# 25632-myersd33_02_7459.net
KiCad netlist of a schematic drawn in Altium Designer
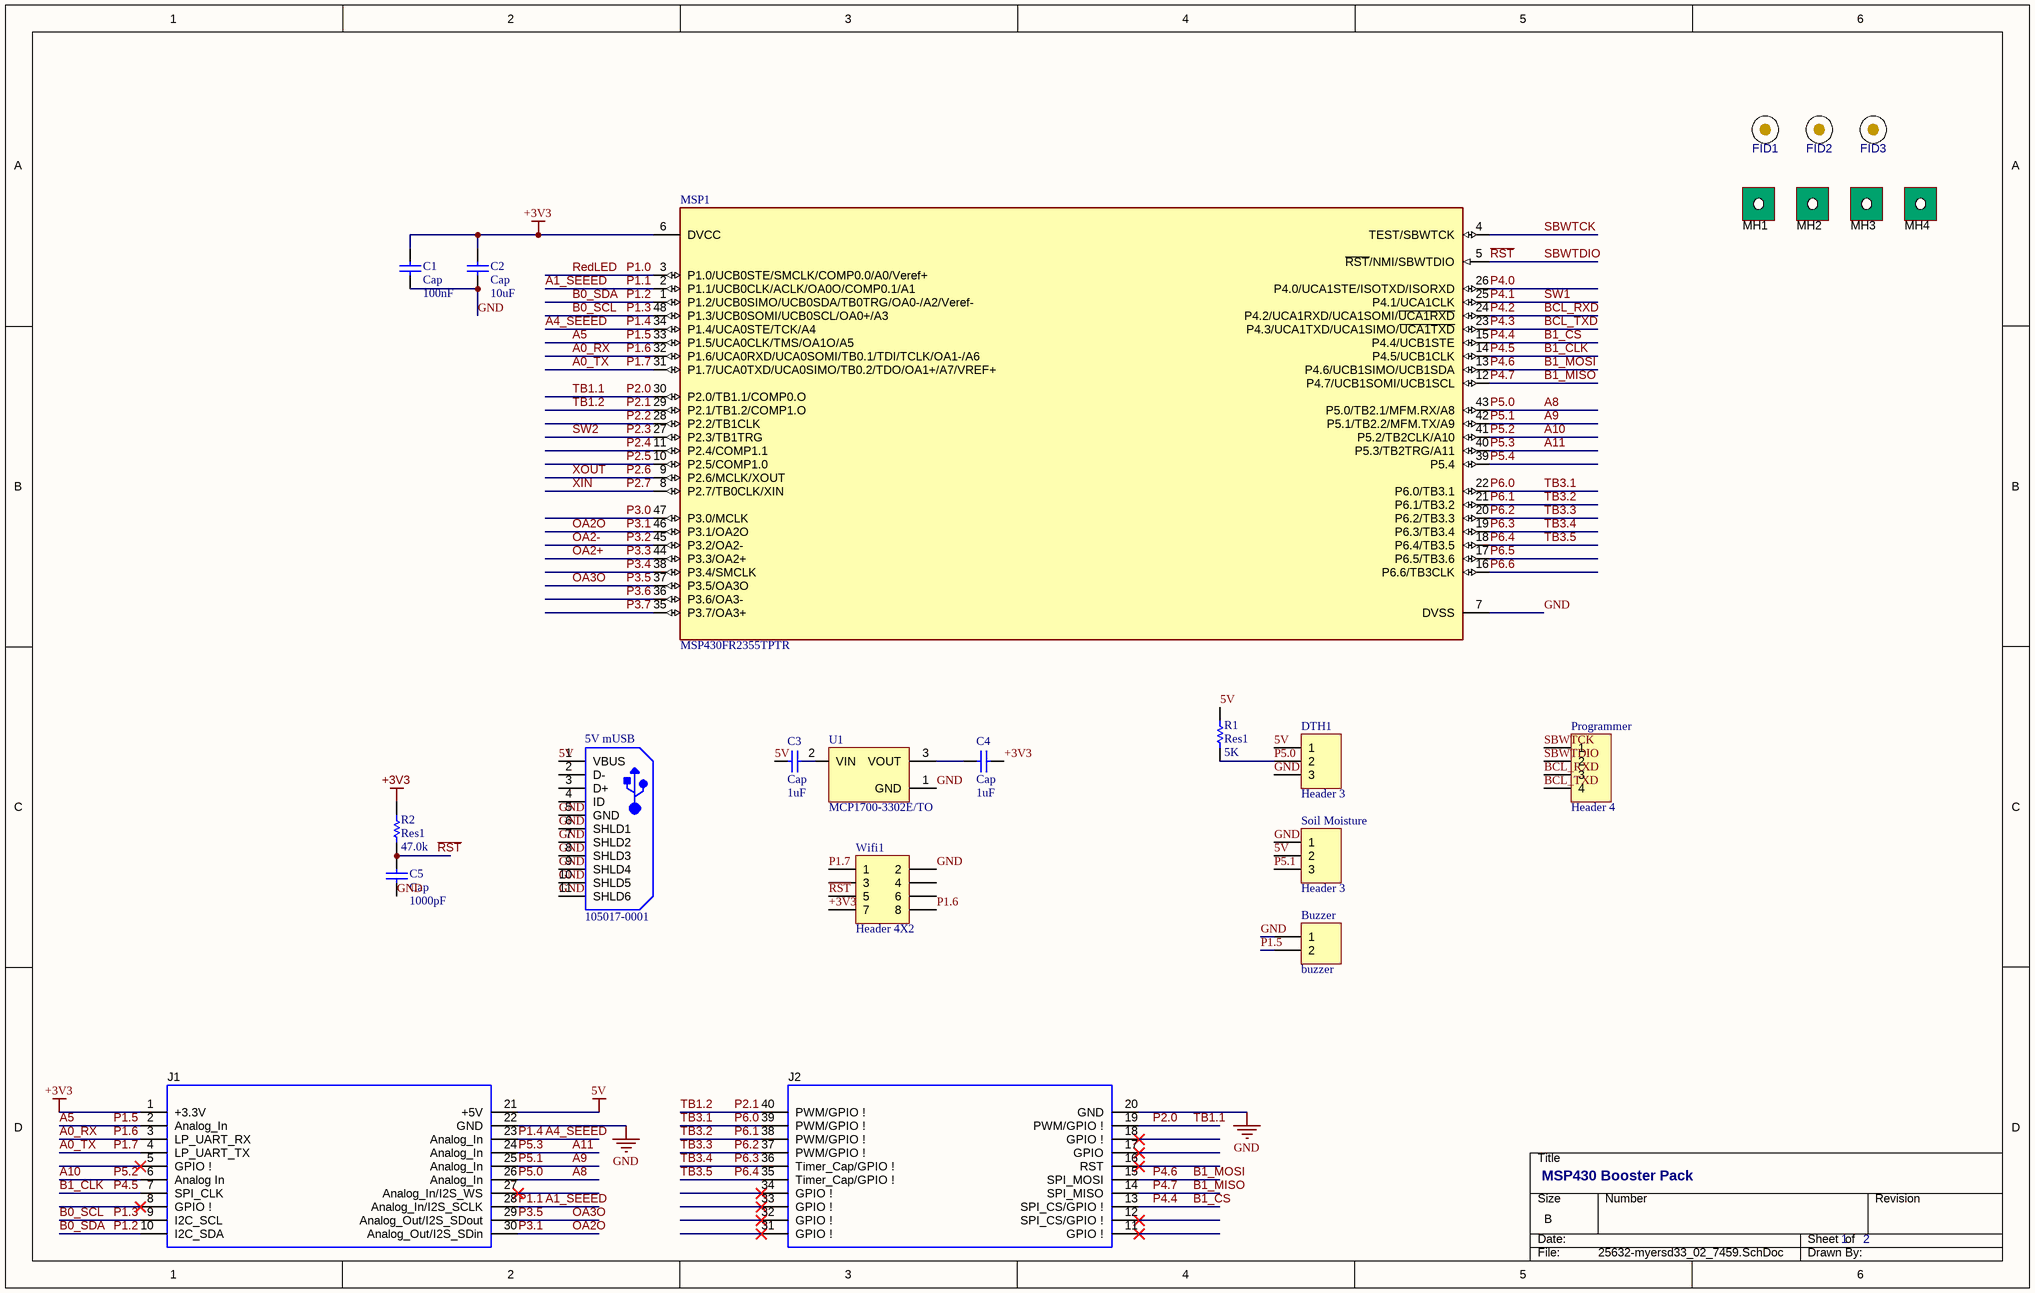
[diagram p0: 25632-myersd33_02_7459.SchDoc]

(export (version "E")
  (design (tool "Eeschema 10.0.6"))
  (components
    (comp (ref "5V mUSB")
      (value "105017-0001")
      (footprint "USB-MICRO-B_V")
      (fields (field (name "MANUFACTURER") "Molex"))
      (libsource (lib "Altium Content Vault") (part "USB-5-6SHLD"))
    )
    (comp (ref "Buzzer")
      (value "buzzer")
      (footprint "HDR1X2")
      (description "Header, 2-Pin")
      (fields (field (name "PUBLISHER") "Altium Limited"))
      (libsource (lib "Miscellaneous Connectors") (part "Header 2"))
    )
    (comp (ref "C1")
      (value "Cap")
      (footprint "RAD-0.3")
      (description "Capacitor")
      (fields (field (name "ALTIUM_VALUE") "100nF") (field (name "PUBLISHER") "Altium Limited"))
      (libsource (lib "Miscellaneous Devices") (part "Cap"))
    )
    (comp (ref "C2")
      (value "Cap")
      (footprint "RAD-0.3")
      (description "Capacitor")
      (fields (field (name "ALTIUM_VALUE") "10uF") (field (name "PUBLISHER") "Altium Limited"))
      (libsource (lib "Miscellaneous Devices") (part "Cap"))
    )
    (comp (ref "C3")
      (value "Cap")
      (footprint "RAD-0.3")
      (description "Capacitor")
      (fields (field (name "ALTIUM_VALUE") "1uF") (field (name "PUBLISHER") "Altium Limited"))
      (libsource (lib "Miscellaneous Devices") (part "Cap"))
    )
    (comp (ref "C4")
      (value "Cap")
      (footprint "RAD-0.3")
      (description "Capacitor")
      (fields (field (name "ALTIUM_VALUE") "1uF") (field (name "PUBLISHER") "Altium Limited"))
      (libsource (lib "Miscellaneous Devices") (part "Cap"))
    )
    (comp (ref "C5")
      (value "Cap")
      (footprint "RAD-0.3")
      (description "Capacitor")
      (fields (field (name "ALTIUM_VALUE") "1000pF") (field (name "PUBLISHER") "Altium Limited"))
      (libsource (lib "Miscellaneous Devices") (part "Cap"))
    )
    (comp (ref "DTH1")
      (value "Header 3")
      (footprint "HDR1X3")
      (description "Header, 3-Pin")
      (fields (field (name "PUBLISHER") "Altium Limited"))
      (libsource (lib "Miscellaneous Connectors") (part "Header 3"))
    )
    (comp (ref "FID1")
      (value "Fiducial")
      (footprint "Fiducial6.4-20")
      (description "Fiducial mark.  There is nothing to buy or mount.")
      (fields (field (name "SYMBOLCREATOR") "codlsc") (field (name "PUBLISHER") "Texas Instruments"))
      (libsource (lib "MiscParts") (part "Fiducial"))
    )
    (comp (ref "FID2")
      (value "Fiducial")
      (footprint "Fiducial6.4-20")
      (description "Fiducial mark.  There is nothing to buy or mount.")
      (fields (field (name "SYMBOLCREATOR") "codlsc") (field (name "PUBLISHER") "Texas Instruments"))
      (libsource (lib "MiscParts") (part "Fiducial"))
    )
    (comp (ref "FID3")
      (value "Fiducial")
      (footprint "Fiducial6.4-20")
      (description "Fiducial mark.  There is nothing to buy or mount.")
      (fields (field (name "SYMBOLCREATOR") "codlsc") (field (name "PUBLISHER") "Texas Instruments"))
      (libsource (lib "MiscParts") (part "Fiducial"))
    )
    (comp (ref "J1")
      (value "SSQ-110-03-T-D")
      (footprint "BoosterPack_40pin_J1J3")
      (description "Receptacle, 2.54mm, 10x2, Tin, TH")
      (fields
        (field (name "MANUFACTURER") "Samtec")
        (field (name "ALTERNATE PARTNUMBER") "CRD-081413-A-G")
        (field (name "SYMBOLCREATOR") "a0412235")
        (field (name "PUBLISHER") "Texas Instruments")
      )
      (libsource (lib "Hardware") (part "BoosterPack_40pin_J1J3"))
    )
    (comp (ref "J2")
      (value "SSQ-110-03-T-D")
      (footprint "BoosterPack_40pin_J2J4")
      (description "Receptacle, 2.54mm, 10x2, Tin, TH")
      (fields
        (field (name "MANUFACTURER") "Samtec")
        (field (name "ALTERNATE PARTNUMBER") "CRD-081413-A-G")
        (field (name "SYMBOLCREATOR") "a0412235")
        (field (name "PUBLISHER") "Texas Instruments")
      )
      (libsource (lib "Hardware") (part "BoosterPack_40pin_J2J4"))
    )
    (comp (ref "MH1")
      (value "MTG_NoPads")
      (footprint "NPTH125mil")
      (description "PCB Mounting Hole, No Pad")
      (fields
        (field (name "MANUFACTURER") "Any")
        (field (name "SYMBOLCREATOR") "a0412235")
        (field (name "PUBLISHER") "Texas Instruments")
      )
      (libsource (lib "Hardware") (part "Mounting Hole (non-standard) No Pad"))
    )
    (comp (ref "MH2")
      (value "MTG_NoPads")
      (footprint "NPTH125mil")
      (description "PCB Mounting Hole, No Pad")
      (fields
        (field (name "MANUFACTURER") "Any")
        (field (name "SYMBOLCREATOR") "a0412235")
        (field (name "PUBLISHER") "Texas Instruments")
      )
      (libsource (lib "Hardware") (part "Mounting Hole (non-standard) No Pad"))
    )
    (comp (ref "MH3")
      (value "MTG_NoPads")
      (footprint "NPTH125mil")
      (description "PCB Mounting Hole, No Pad")
      (fields
        (field (name "MANUFACTURER") "Any")
        (field (name "SYMBOLCREATOR") "a0412235")
        (field (name "PUBLISHER") "Texas Instruments")
      )
      (libsource (lib "Hardware") (part "Mounting Hole (non-standard) No Pad"))
    )
    (comp (ref "MH4")
      (value "MTG_NoPads")
      (footprint "NPTH125mil")
      (description "PCB Mounting Hole, No Pad")
      (fields
        (field (name "MANUFACTURER") "Any")
        (field (name "SYMBOLCREATOR") "a0412235")
        (field (name "PUBLISHER") "Texas Instruments")
      )
      (libsource (lib "Hardware") (part "Mounting Hole (non-standard) No Pad"))
    )
    (comp (ref "MSP1")
      (value "MSP430FR2355TPTR")
      (footprint "FP-PT0048A-MFG")
      (description "IC MCU 16BIT 32KB FRAM 48LQFP")
      (fields
        (field (name "MANUFACTURER") "Texas Instruments")
        (field (name "OCTOPART") "https://octopart.com/msp430fr2355tptr-texas+instruments-92191342")
      )
      (libsource (lib "Altium Content Vault") (part "bd983ca6877cdd146f198514b3acb3b"))
    )
    (comp (ref "Programmer")
      (value "Header 4")
      (footprint "HDR1X4")
      (description "Header, 4-Pin")
      (fields (field (name "PUBLISHER") "Altium Limited"))
      (libsource (lib "Miscellaneous Connectors") (part "Header 4"))
    )
    (comp (ref "R1")
      (value "Res1")
      (footprint "AXIAL-0.3")
      (description "Resistor")
      (fields (field (name "ALTIUM_VALUE") "5K") (field (name "PUBLISHER") "Altium Limited"))
      (libsource (lib "Miscellaneous Devices") (part "Res1"))
    )
    (comp (ref "R2")
      (value "Res1")
      (footprint "AXIAL-0.3")
      (description "Resistor")
      (fields (field (name "ALTIUM_VALUE") "47.0k") (field (name "PUBLISHER") "Altium Limited"))
      (libsource (lib "Miscellaneous Devices") (part "Res1"))
    )
    (comp (ref "Soil Moisture")
      (value "Header 3")
      (footprint "HDR1X3")
      (description "Header, 3-Pin")
      (fields (field (name "PUBLISHER") "Altium Limited"))
      (libsource (lib "Miscellaneous Connectors") (part "Header 3"))
    )
    (comp (ref "U1")
      (value "MCP1700-3302E/TO")
      (footprint "TO-92-TO3")
      (description "Low Quiescent Current LDO, 3-Pin TO-92, Extended TemperatureBAG")
      (libsource (lib "Altium Content Vault") (part "PM-LINEREG-MCP1700-IL3B"))
    )
    (comp (ref "Wifi1")
      (value "Header 4X2")
      (footprint "HDR2X4")
      (description "Header, 4-Pin, Dual row")
      (fields (field (name "PUBLISHER") "Altium Limited"))
      (libsource (lib "Miscellaneous Connectors") (part "Header 4X2"))
    )
  )
  (nets
    (net (code "1") (name "+3V3") (class "Default")
      (node (ref "C1") (pin "2") (pinfunction "2_2") (pintype "passive"))
      (node (ref "C2") (pin "2") (pinfunction "2_2") (pintype "passive"))
      (node (ref "C4") (pin "2") (pinfunction "2_2") (pintype "passive"))
      (node (ref "J1") (pin "1") (pinfunction "+3.3V_1") (pintype "power_in"))
      (node (ref "MSP1") (pin "6") (pinfunction "DVCC_6") (pintype "power_in"))
      (node (ref "R2") (pin "2") (pinfunction "2_2") (pintype "passive"))
      (node (ref "Wifi1") (pin "7") (pinfunction "7_7") (pintype "passive"))
    )
    (net (code "2") (name "/A0_RX") (class "Default")
      (node (ref "J1") (pin "3") (pinfunction "LP_UART_RX_3") (pintype "passive"))
      (node (ref "MSP1") (pin "32") (pinfunction "P1.6/UCA0RXD/UCA0SOMI/TB0.1/TDI/TCLK/OA1-/A6_32") (pintype "bidirectional"))
      (node (ref "Wifi1") (pin "8") (pinfunction "8_8") (pintype "passive"))
    )
    (net (code "3") (name "/A0_TX") (class "Default")
      (node (ref "J1") (pin "4") (pinfunction "LP_UART_TX_4") (pintype "passive"))
      (node (ref "MSP1") (pin "31") (pinfunction "P1.7/UCA0TXD/UCA0SIMO/TB0.2/TDO/OA1+/A7/VREF+_31") (pintype "bidirectional"))
      (node (ref "Wifi1") (pin "1") (pinfunction "1_1") (pintype "passive"))
    )
    (net (code "4") (name "/A1_SEEED") (class "Default")
      (node (ref "J1") (pin "28") (pinfunction "Analog_In/I2S_SCLK_28") (pintype "passive"))
      (node (ref "MSP1") (pin "2") (pinfunction "P1.1/UCB0CLK/ACLK/OA0O/COMP0.1/A1_2") (pintype "bidirectional"))
    )
    (net (code "5") (name "/A4_SEEED") (class "Default")
      (node (ref "J1") (pin "23") (pinfunction "Analog_In_23") (pintype "passive"))
      (node (ref "MSP1") (pin "34") (pinfunction "P1.4/UCA0STE/TCK/A4_34") (pintype "bidirectional"))
    )
    (net (code "6") (name "/A5") (class "Default")
      (node (ref "Buzzer") (pin "2") (pinfunction "2_2") (pintype "passive"))
      (node (ref "J1") (pin "2") (pinfunction "Analog_In_2") (pintype "passive"))
      (node (ref "MSP1") (pin "33") (pinfunction "P1.5/UCA0CLK/TMS/OA1O/A5_33") (pintype "bidirectional"))
    )
    (net (code "7") (name "/A8") (class "Default")
      (node (ref "DTH1") (pin "2") (pinfunction "2_2") (pintype "passive"))
      (node (ref "J1") (pin "26") (pinfunction "Analog_In_26") (pintype "passive"))
      (node (ref "MSP1") (pin "43") (pinfunction "P5.0/TB2.1/MFM.RX/A8_43") (pintype "bidirectional"))
      (node (ref "R1") (pin "1") (pinfunction "1_1") (pintype "passive"))
    )
    (net (code "8") (name "/A9") (class "Default")
      (node (ref "J1") (pin "25") (pinfunction "Analog_In_25") (pintype "passive"))
      (node (ref "MSP1") (pin "42") (pinfunction "P5.1/TB2.2/MFM.TX/A9_42") (pintype "bidirectional"))
      (node (ref "Soil Moisture") (pin "3") (pinfunction "3_3") (pintype "passive"))
    )
    (net (code "9") (name "/A10") (class "Default")
      (node (ref "J1") (pin "6") (pinfunction "Analog_In_6") (pintype "passive"))
      (node (ref "MSP1") (pin "41") (pinfunction "P5.2/TB2CLK/A10_41") (pintype "bidirectional"))
    )
    (net (code "10") (name "/A11") (class "Default")
      (node (ref "J1") (pin "24") (pinfunction "Analog_In_24") (pintype "passive"))
      (node (ref "MSP1") (pin "40") (pinfunction "P5.3/TB2TRG/A11_40") (pintype "bidirectional"))
    )
    (net (code "11") (name "/B0_SCL") (class "Default")
      (node (ref "J1") (pin "9") (pinfunction "I2C_SCL_9") (pintype "passive"))
      (node (ref "MSP1") (pin "48") (pinfunction "P1.3/UCB0SOMI/UCB0SCL/OA0+/A3_48") (pintype "bidirectional"))
    )
    (net (code "12") (name "/B0_SDA") (class "Default")
      (node (ref "J1") (pin "10") (pinfunction "I2C_SDA_10") (pintype "passive"))
      (node (ref "MSP1") (pin "1") (pinfunction "P1.2/UCB0SIMO/UCB0SDA/TB0TRG/OA0-/A2/Veref-_1") (pintype "bidirectional"))
    )
    (net (code "13") (name "/B1_CLK") (class "Default")
      (node (ref "J1") (pin "7") (pinfunction "SPI_CLK_7") (pintype "passive"))
      (node (ref "MSP1") (pin "14") (pinfunction "P4.5/UCB1CLK_14") (pintype "bidirectional"))
    )
    (net (code "14") (name "/B1_CS") (class "Default")
      (node (ref "J2") (pin "13") (pinfunction "SPI_CS/GPIO_!_13") (pintype "passive"))
      (node (ref "MSP1") (pin "15") (pinfunction "P4.4/UCB1STE_15") (pintype "bidirectional"))
    )
    (net (code "15") (name "/B1_MISO") (class "Default")
      (node (ref "J2") (pin "14") (pinfunction "SPI_MISO_14") (pintype "passive"))
      (node (ref "MSP1") (pin "12") (pinfunction "P4.7/UCB1SOMI/UCB1SCL_12") (pintype "bidirectional"))
    )
    (net (code "16") (name "/B1_MOSI") (class "Default")
      (node (ref "J2") (pin "15") (pinfunction "SPI_MOSI_15") (pintype "passive"))
      (node (ref "MSP1") (pin "13") (pinfunction "P4.6/UCB1SIMO/UCB1SDA_13") (pintype "bidirectional"))
    )
    (net (code "17") (name "/BCL_RXD") (class "Default")
      (node (ref "MSP1") (pin "24") (pinfunction "P4.2/UCA1RXD/UCA1SOMI/~{UCA1RXD}_24") (pintype "bidirectional"))
      (node (ref "Programmer") (pin "3") (pinfunction "3_3") (pintype "passive"))
    )
    (net (code "18") (name "/BCL_TXD") (class "Default")
      (node (ref "MSP1") (pin "23") (pinfunction "P4.3/UCA1TXD/UCA1SIMO/~{UCA1TXD}_23") (pintype "bidirectional"))
      (node (ref "Programmer") (pin "4") (pinfunction "4_4") (pintype "passive"))
    )
    (net (code "19") (name "/OA2+") (class "Default")
      (node (ref "MSP1") (pin "44") (pinfunction "P3.3/OA2+_44") (pintype "bidirectional"))
    )
    (net (code "20") (name "/OA2-") (class "Default")
      (node (ref "MSP1") (pin "45") (pinfunction "P3.2/OA2-_45") (pintype "bidirectional"))
    )
    (net (code "21") (name "/OA2O") (class "Default")
      (node (ref "J1") (pin "30") (pinfunction "Analog_Out/I2S_SDin_30") (pintype "passive"))
      (node (ref "MSP1") (pin "46") (pinfunction "P3.1/OA2O_46") (pintype "bidirectional"))
    )
    (net (code "22") (name "/OA3O") (class "Default")
      (node (ref "J1") (pin "29") (pinfunction "Analog_Out/I2S_SDout_29") (pintype "passive"))
      (node (ref "MSP1") (pin "37") (pinfunction "P3.5/OA3O_37") (pintype "bidirectional"))
    )
    (net (code "23") (name "/P1.0") (class "Default")
      (node (ref "MSP1") (pin "3") (pinfunction "P1.0/UCB0STE/SMCLK/COMP0.0/A0/Veref+_3") (pintype "bidirectional"))
    )
    (net (code "24") (name "/P2.0") (class "Default")
      (node (ref "J2") (pin "19") (pinfunction "PWM/GPIO_!_19") (pintype "passive"))
      (node (ref "MSP1") (pin "30") (pinfunction "P2.0/TB1.1/COMP0.O_30") (pintype "bidirectional"))
    )
    (net (code "25") (name "/P2.1") (class "Default")
      (node (ref "J2") (pin "40") (pinfunction "PWM/GPIO_!_40") (pintype "passive"))
      (node (ref "MSP1") (pin "29") (pinfunction "P2.1/TB1.2/COMP1.O_29") (pintype "bidirectional"))
    )
    (net (code "26") (name "/P2.2") (class "Default")
      (node (ref "MSP1") (pin "28") (pinfunction "P2.2/TB1CLK_28") (pintype "bidirectional"))
    )
    (net (code "27") (name "/P2.3") (class "Default")
      (node (ref "MSP1") (pin "27") (pinfunction "P2.3/TB1TRG_27") (pintype "bidirectional"))
    )
    (net (code "28") (name "/P2.4") (class "Default")
      (node (ref "MSP1") (pin "11") (pinfunction "P2.4/COMP1.1_11") (pintype "bidirectional"))
    )
    (net (code "29") (name "/P2.5") (class "Default")
      (node (ref "MSP1") (pin "10") (pinfunction "P2.5/COMP1.0_10") (pintype "bidirectional"))
    )
    (net (code "30") (name "/P2.6") (class "Default")
      (node (ref "MSP1") (pin "9") (pinfunction "P2.6/MCLK/XOUT_9") (pintype "bidirectional"))
    )
    (net (code "31") (name "/P2.7") (class "Default")
      (node (ref "MSP1") (pin "8") (pinfunction "P2.7/TB0CLK/XIN_8") (pintype "bidirectional"))
    )
    (net (code "32") (name "/P3.0") (class "Default")
      (node (ref "MSP1") (pin "47") (pinfunction "P3.0/MCLK_47") (pintype "bidirectional"))
    )
    (net (code "33") (name "/P3.4") (class "Default")
      (node (ref "MSP1") (pin "38") (pinfunction "P3.4/SMCLK_38") (pintype "bidirectional"))
    )
    (net (code "34") (name "/P3.6") (class "Default")
      (node (ref "MSP1") (pin "36") (pinfunction "P3.6/OA3-_36") (pintype "bidirectional"))
    )
    (net (code "35") (name "/P3.7") (class "Default")
      (node (ref "MSP1") (pin "35") (pinfunction "P3.7/OA3+_35") (pintype "bidirectional"))
    )
    (net (code "36") (name "/P4.0") (class "Default")
      (node (ref "MSP1") (pin "26") (pinfunction "P4.0/UCA1STE/ISOTXD/ISORXD_26") (pintype "bidirectional"))
    )
    (net (code "37") (name "/P4.1") (class "Default")
      (node (ref "MSP1") (pin "25") (pinfunction "P4.1/UCA1CLK_25") (pintype "bidirectional"))
    )
    (net (code "38") (name "/P5.4") (class "Default")
      (node (ref "MSP1") (pin "39") (pinfunction "P5.4_39") (pintype "bidirectional"))
    )
    (net (code "39") (name "/P6.0") (class "Default")
      (node (ref "J2") (pin "39") (pinfunction "PWM/GPIO_!_39") (pintype "passive"))
      (node (ref "MSP1") (pin "22") (pinfunction "P6.0/TB3.1_22") (pintype "bidirectional"))
    )
    (net (code "40") (name "/P6.1") (class "Default")
      (node (ref "J2") (pin "38") (pinfunction "PWM/GPIO_!_38") (pintype "passive"))
      (node (ref "MSP1") (pin "21") (pinfunction "P6.1/TB3.2_21") (pintype "bidirectional"))
    )
    (net (code "41") (name "/P6.2") (class "Default")
      (node (ref "J2") (pin "37") (pinfunction "PWM/GPIO_!_37") (pintype "passive"))
      (node (ref "MSP1") (pin "20") (pinfunction "P6.2/TB3.3_20") (pintype "bidirectional"))
    )
    (net (code "42") (name "/P6.3") (class "Default")
      (node (ref "J2") (pin "36") (pinfunction "Timer_Cap/GPIO_!_36") (pintype "passive"))
      (node (ref "MSP1") (pin "19") (pinfunction "P6.3/TB3.4_19") (pintype "bidirectional"))
    )
    (net (code "43") (name "/P6.4") (class "Default")
      (node (ref "J2") (pin "35") (pinfunction "Timer_Cap/GPIO_!_35") (pintype "passive"))
      (node (ref "MSP1") (pin "18") (pinfunction "P6.4/TB3.5_18") (pintype "bidirectional"))
    )
    (net (code "44") (name "/P6.5") (class "Default")
      (node (ref "MSP1") (pin "17") (pinfunction "P6.5/TB3.6_17") (pintype "bidirectional"))
    )
    (net (code "45") (name "/P6.6") (class "Default")
      (node (ref "MSP1") (pin "16") (pinfunction "P6.6/TB3CLK_16") (pintype "bidirectional"))
    )
    (net (code "46") (name "/SBWTCK") (class "Default")
      (node (ref "MSP1") (pin "4") (pinfunction "TEST/SBWTCK_4") (pintype "bidirectional"))
      (node (ref "Programmer") (pin "1") (pinfunction "1_1") (pintype "passive"))
    )
    (net (code "47") (name "/SBWTDIO") (class "Default")
      (node (ref "C5") (pin "2") (pinfunction "2_2") (pintype "passive"))
      (node (ref "MSP1") (pin "5") (pinfunction "~{RST}/NMI/SBWTDIO_5") (pintype "input"))
      (node (ref "Programmer") (pin "2") (pinfunction "2_2") (pintype "passive"))
      (node (ref "R2") (pin "1") (pinfunction "1_1") (pintype "passive"))
      (node (ref "Wifi1") (pin "5") (pinfunction "5_5") (pintype "passive"))
    )
    (net (code "48") (name "5V") (class "Default")
      (node (ref "5V mUSB") (pin "1") (pinfunction "VBUS_1") (pintype "passive"))
      (node (ref "C3") (pin "1") (pinfunction "1_1") (pintype "passive"))
      (node (ref "DTH1") (pin "1") (pinfunction "1_1") (pintype "passive"))
      (node (ref "J1") (pin "21") (pinfunction "+5V_21") (pintype "power_in"))
      (node (ref "R1") (pin "2") (pinfunction "2_2") (pintype "passive"))
      (node (ref "Soil Moisture") (pin "2") (pinfunction "2_2") (pintype "passive"))
    )
    (net (code "49") (name "GND") (class "Default")
      (node (ref "5V mUSB") (pin "10") (pinfunction "SHLD5_10") (pintype "passive"))
      (node (ref "5V mUSB") (pin "11") (pinfunction "SHLD6_11") (pintype "passive"))
      (node (ref "5V mUSB") (pin "5") (pinfunction "GND_5") (pintype "passive"))
      (node (ref "5V mUSB") (pin "6") (pinfunction "SHLD1_6") (pintype "passive"))
      (node (ref "5V mUSB") (pin "7") (pinfunction "SHLD2_7") (pintype "passive"))
      (node (ref "5V mUSB") (pin "8") (pinfunction "SHLD3_8") (pintype "passive"))
      (node (ref "5V mUSB") (pin "9") (pinfunction "SHLD4_9") (pintype "passive"))
      (node (ref "Buzzer") (pin "1") (pinfunction "1_1") (pintype "passive"))
      (node (ref "C1") (pin "1") (pinfunction "1_1") (pintype "passive"))
      (node (ref "C2") (pin "1") (pinfunction "1_1") (pintype "passive"))
      (node (ref "C5") (pin "1") (pinfunction "1_1") (pintype "passive"))
      (node (ref "DTH1") (pin "3") (pinfunction "3_3") (pintype "passive"))
      (node (ref "J1") (pin "22") (pinfunction "GND_22") (pintype "power_in"))
      (node (ref "J2") (pin "20") (pinfunction "GND_20") (pintype "power_in"))
      (node (ref "MSP1") (pin "7") (pinfunction "DVSS_7") (pintype "power_in"))
      (node (ref "Soil Moisture") (pin "1") (pinfunction "1_1") (pintype "passive"))
      (node (ref "U1") (pin "1") (pinfunction "GND_1") (pintype "power_in"))
      (node (ref "Wifi1") (pin "2") (pinfunction "2_2") (pintype "passive"))
    )
    (net (code "50") (name "Net-(U1-VIN)") (class "Default")
      (node (ref "C3") (pin "2") (pinfunction "2_2") (pintype "passive"))
      (node (ref "U1") (pin "2") (pinfunction "VIN_2") (pintype "power_in"))
    )
    (net (code "51") (name "Net-(U1-VOUT)") (class "Default")
      (node (ref "C4") (pin "1") (pinfunction "1_1") (pintype "passive"))
      (node (ref "U1") (pin "3") (pinfunction "VOUT_3") (pintype "power_in"))
    )
    (net (code "52") (name "unconnected-(5V mUSB-D+-Pad3)") (class "Default")
      (node (ref "5V mUSB") (pin "3") (pinfunction "D+_3") (pintype "passive"))
    )
    (net (code "53") (name "unconnected-(5V mUSB-D--Pad2)") (class "Default")
      (node (ref "5V mUSB") (pin "2") (pinfunction "D-_2") (pintype "passive"))
    )
    (net (code "54") (name "unconnected-(5V mUSB-ID-Pad4)") (class "Default")
      (node (ref "5V mUSB") (pin "4") (pinfunction "ID_4") (pintype "passive"))
    )
    (net (code "55") (name "unconnected-(J1-Analog_In{slash}I2S_WS-Pad27)") (class "Default")
      (node (ref "J1") (pin "27") (pinfunction "Analog_In/I2S_WS_27") (pintype "passive+no_connect"))
    )
    (net (code "56") (name "unconnected-(J1-GPIO_!-Pad5)") (class "Default")
      (node (ref "J1") (pin "5") (pinfunction "GPIO_!_5") (pintype "passive+no_connect"))
    )
    (net (code "57") (name "unconnected-(J1-GPIO_!-Pad8)") (class "Default")
      (node (ref "J1") (pin "8") (pinfunction "GPIO_!_8") (pintype "passive+no_connect"))
    )
    (net (code "58") (name "unconnected-(J2-GPIO-Pad17)") (class "Default")
      (node (ref "J2") (pin "17") (pinfunction "GPIO_17") (pintype "passive+no_connect"))
    )
    (net (code "59") (name "unconnected-(J2-GPIO_!-Pad11)") (class "Default")
      (node (ref "J2") (pin "11") (pinfunction "GPIO_!_11") (pintype "passive+no_connect"))
    )
    (net (code "60") (name "unconnected-(J2-GPIO_!-Pad18)") (class "Default")
      (node (ref "J2") (pin "18") (pinfunction "GPIO_!_18") (pintype "passive+no_connect"))
    )
    (net (code "61") (name "unconnected-(J2-GPIO_!-Pad31)") (class "Default")
      (node (ref "J2") (pin "31") (pinfunction "GPIO_!_31") (pintype "passive+no_connect"))
    )
    (net (code "62") (name "unconnected-(J2-GPIO_!-Pad32)") (class "Default")
      (node (ref "J2") (pin "32") (pinfunction "GPIO_!_32") (pintype "passive+no_connect"))
    )
    (net (code "63") (name "unconnected-(J2-GPIO_!-Pad33)") (class "Default")
      (node (ref "J2") (pin "33") (pinfunction "GPIO_!_33") (pintype "passive+no_connect"))
    )
    (net (code "64") (name "unconnected-(J2-GPIO_!-Pad34)") (class "Default")
      (node (ref "J2") (pin "34") (pinfunction "GPIO_!_34") (pintype "passive+no_connect"))
    )
    (net (code "65") (name "unconnected-(J2-RST-Pad16)") (class "Default")
      (node (ref "J2") (pin "16") (pinfunction "RST_16") (pintype "passive+no_connect"))
    )
    (net (code "66") (name "unconnected-(J2-SPI_CS{slash}GPIO_!-Pad12)") (class "Default")
      (node (ref "J2") (pin "12") (pinfunction "SPI_CS/GPIO_!_12") (pintype "passive+no_connect"))
    )
    (net (code "67") (name "unconnected-(Wifi1-Pad3)") (class "Default")
      (node (ref "Wifi1") (pin "3") (pinfunction "3_3") (pintype "passive"))
    )
    (net (code "68") (name "unconnected-(Wifi1-Pad4)") (class "Default")
      (node (ref "Wifi1") (pin "4") (pinfunction "4_4") (pintype "passive"))
    )
    (net (code "69") (name "unconnected-(Wifi1-Pad6)") (class "Default")
      (node (ref "Wifi1") (pin "6") (pinfunction "6_6") (pintype "passive"))
    )
  )
)
